# Hot.net
KiCad netlist of a schematic drawn in EAGLE
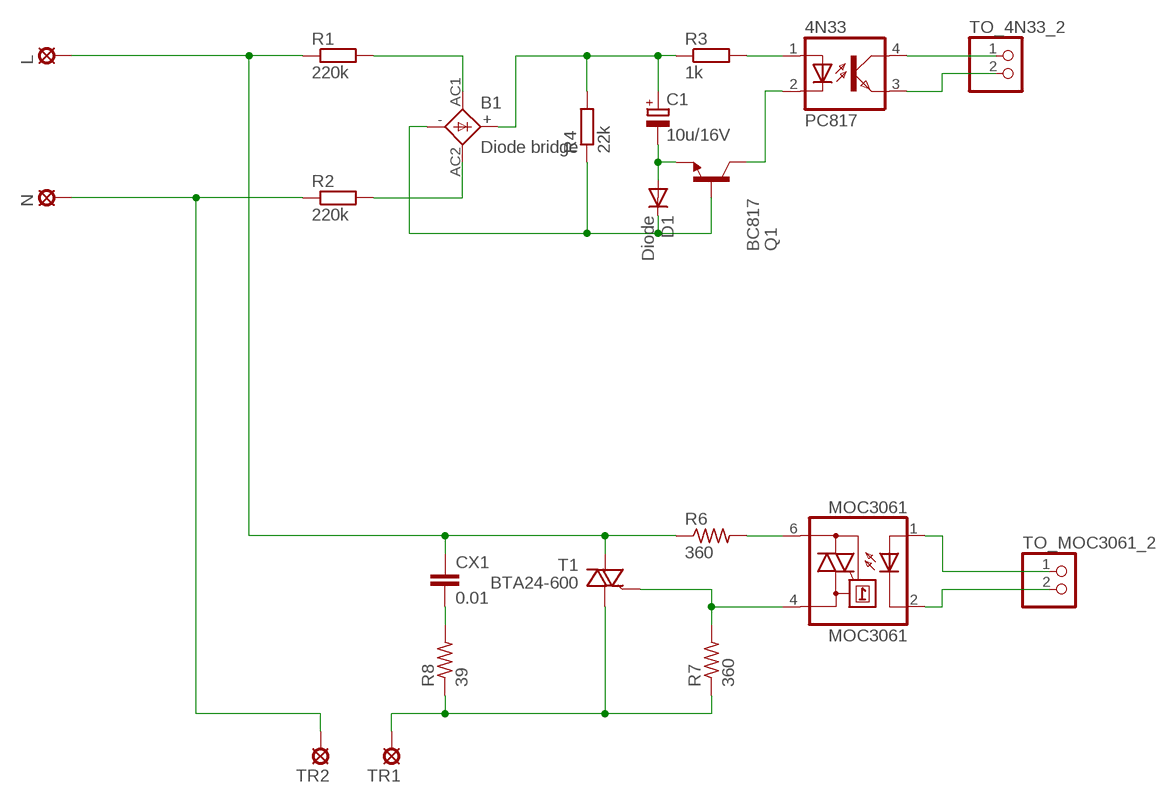
[diagram p0: schematic, sheet 1]

(export (version "E")
  (design (tool "Eeschema 10.0.6"))
  (components
    (comp (ref "4N33")
      (value "PC817")
      (footprint "eagle-import:DIL04")
      (libsource (lib "eagle-import") (part "PC817"))
    )
    (comp (ref "B1")
      (value "Diode bridge")
      (footprint "eagle-import:2KBB-R")
      (libsource (lib "eagle-import") (part "2KBB-R"))
    )
    (comp (ref "C1")
      (value "10u/16V")
      (footprint "eagle-import:E2,5-5")
      (libsource (lib "eagle-import") (part "CPOL-EUE2.5-5"))
    )
    (comp (ref "CX1")
      (value "0.01")
      (footprint "eagle-import:XC10B6")
      (libsource (lib "eagle-import") (part "CXXC10B6"))
    )
    (comp (ref "D1")
      (value "Diode")
      (footprint "eagle-import:DO-214AC")
      (libsource (lib "eagle-import") (part "DIODE-DO-214AC"))
    )
    (comp (ref "L")
      (value "LSP10")
      (footprint "eagle-import:LSP10")
      (libsource (lib "eagle-import") (part "LSP10"))
    )
    (comp (ref "MOC3061")
      (value "MOC3061")
      (footprint "eagle-import:DIL06")
      (libsource (lib "eagle-import") (part "IL410"))
    )
    (comp (ref "N")
      (value "LSP10")
      (footprint "eagle-import:LSP10")
      (libsource (lib "eagle-import") (part "LSP10"))
    )
    (comp (ref "Q1")
      (value "BC817")
      (footprint "eagle-import:SOT23-BEC")
      (libsource (lib "eagle-import") (part "BC817SMD-16LT1"))
    )
    (comp (ref "R1")
      (value "220k")
      (footprint "eagle-import:M1206")
      (libsource (lib "eagle-import") (part "R-EU_M1206"))
    )
    (comp (ref "R2")
      (value "220k")
      (footprint "eagle-import:M1206")
      (libsource (lib "eagle-import") (part "R-EU_M1206"))
    )
    (comp (ref "R3")
      (value "1k")
      (footprint "eagle-import:M1206")
      (libsource (lib "eagle-import") (part "R-EU_M1206"))
    )
    (comp (ref "R4")
      (value "22k")
      (footprint "eagle-import:M1206")
      (libsource (lib "eagle-import") (part "R-EU_M1206"))
    )
    (comp (ref "R6")
      (value "360")
      (footprint "eagle-import:VTA54")
      (libsource (lib "eagle-import") (part "R-US_VTA54"))
    )
    (comp (ref "R7")
      (value "360")
      (footprint "eagle-import:VTA54")
      (libsource (lib "eagle-import") (part "R-US_VTA54"))
    )
    (comp (ref "R8")
      (value "39")
      (footprint "eagle-import:VTA52")
      (libsource (lib "eagle-import") (part "R-US_VTA52"))
    )
    (comp (ref "T1")
      (value "BTA24-600")
      (footprint "eagle-import:TO220DS")
      (libsource (lib "eagle-import") (part "TIC225S"))
    )
    (comp (ref "TO_4N33_2")
      (value "PINHD-1X2")
      (footprint "eagle-import:1X02")
      (libsource (lib "eagle-import") (part "PINHD-1X2"))
    )
    (comp (ref "TO_MOC3061_2")
      (value "PINHD-1X2")
      (footprint "eagle-import:1X02")
      (libsource (lib "eagle-import") (part "PINHD-1X2"))
    )
    (comp (ref "TR1")
      (value "LSP10")
      (footprint "eagle-import:LSP10")
      (libsource (lib "eagle-import") (part "LSP10"))
    )
    (comp (ref "TR2")
      (value "LSP10")
      (footprint "eagle-import:LSP10")
      (libsource (lib "eagle-import") (part "LSP10"))
    )
  )
  (nets
    (net (code "1") (name "Net-(4N33-A)") (class "Default")
      (node (ref "4N33") (pin "1") (pinfunction "A_1") (pintype "passive"))
      (node (ref "R3") (pin "2") (pinfunction "2_2") (pintype "passive"))
    )
    (net (code "2") (name "Net-(4N33-C)") (class "Default")
      (node (ref "4N33") (pin "2") (pinfunction "C_2") (pintype "passive"))
      (node (ref "Q1") (pin "C") (pinfunction "C_C") (pintype "passive"))
    )
    (net (code "3") (name "Net-(4N33-COL)") (class "Default")
      (node (ref "4N33") (pin "4") (pinfunction "COL_4") (pintype "passive"))
      (node (ref "TO_4N33_2") (pin "1") (pinfunction "1_1") (pintype "passive"))
    )
    (net (code "4") (name "Net-(4N33-EMIT)") (class "Default")
      (node (ref "4N33") (pin "3") (pinfunction "EMIT_3") (pintype "passive"))
      (node (ref "TO_4N33_2") (pin "2") (pinfunction "2_2") (pintype "passive"))
    )
    (net (code "5") (name "Net-(B1-Pad+)") (class "Default")
      (node (ref "B1") (pin "+") (pinfunction "+_+") (pintype "passive"))
      (node (ref "C1") (pin "+") (pinfunction "+_+") (pintype "passive"))
      (node (ref "R3") (pin "1") (pinfunction "1_1") (pintype "passive"))
      (node (ref "R4") (pin "2") (pinfunction "2_2") (pintype "passive"))
    )
    (net (code "6") (name "Net-(B1-Pad-)") (class "Default")
      (node (ref "B1") (pin "-") (pinfunction "-_-") (pintype "passive"))
      (node (ref "D1") (pin "C") (pinfunction "C_C") (pintype "passive"))
      (node (ref "Q1") (pin "B") (pinfunction "B_B") (pintype "passive"))
      (node (ref "R4") (pin "1") (pinfunction "1_1") (pintype "passive"))
    )
    (net (code "7") (name "Net-(B1-PadAC1)") (class "Default")
      (node (ref "B1") (pin "AC1") (pinfunction "AC1_AC1") (pintype "passive"))
      (node (ref "R1") (pin "2") (pinfunction "2_2") (pintype "passive"))
    )
    (net (code "8") (name "Net-(B1-PadAC2)") (class "Default")
      (node (ref "B1") (pin "AC2") (pinfunction "AC2_AC2") (pintype "passive"))
      (node (ref "R2") (pin "2") (pinfunction "2_2") (pintype "passive"))
    )
    (net (code "9") (name "Net-(C1-Pad-)") (class "Default")
      (node (ref "C1") (pin "-") (pinfunction "-_-") (pintype "passive"))
      (node (ref "D1") (pin "A") (pinfunction "A_A") (pintype "passive"))
      (node (ref "Q1") (pin "E") (pinfunction "E_E") (pintype "passive"))
    )
    (net (code "10") (name "Net-(CX1-Pad1)") (class "Default")
      (node (ref "CX1") (pin "1") (pinfunction "1_1") (pintype "passive"))
      (node (ref "L") (pin "MP") (pinfunction "MP_MP") (pintype "passive"))
      (node (ref "R1") (pin "1") (pinfunction "1_1") (pintype "passive"))
      (node (ref "R6") (pin "1") (pinfunction "1_1") (pintype "passive"))
      (node (ref "T1") (pin "A2") (pinfunction "A2_A2") (pintype "passive"))
    )
    (net (code "11") (name "Net-(CX1-Pad2)") (class "Default")
      (node (ref "CX1") (pin "2") (pinfunction "2_2") (pintype "passive"))
      (node (ref "R8") (pin "2") (pinfunction "2_2") (pintype "passive"))
    )
    (net (code "12") (name "Net-(MOC3061-A)") (class "Default")
      (node (ref "MOC3061") (pin "1") (pinfunction "A_1") (pintype "passive"))
      (node (ref "TO_MOC3061_2") (pin "1") (pinfunction "1_1") (pintype "passive"))
    )
    (net (code "13") (name "Net-(MOC3061-A1)") (class "Default")
      (node (ref "MOC3061") (pin "4") (pinfunction "A1_4") (pintype "passive"))
      (node (ref "R7") (pin "2") (pinfunction "2_2") (pintype "passive"))
      (node (ref "T1") (pin "G") (pinfunction "G_G") (pintype "passive"))
    )
    (net (code "14") (name "Net-(MOC3061-A2)") (class "Default")
      (node (ref "MOC3061") (pin "6") (pinfunction "A2_6") (pintype "passive"))
      (node (ref "R6") (pin "2") (pinfunction "2_2") (pintype "passive"))
    )
    (net (code "15") (name "Net-(MOC3061-C)") (class "Default")
      (node (ref "MOC3061") (pin "2") (pinfunction "C_2") (pintype "passive"))
      (node (ref "TO_MOC3061_2") (pin "2") (pinfunction "2_2") (pintype "passive"))
    )
    (net (code "16") (name "Net-(N-PadMP)") (class "Default")
      (node (ref "N") (pin "MP") (pinfunction "MP_MP") (pintype "passive"))
      (node (ref "R2") (pin "1") (pinfunction "1_1") (pintype "passive"))
      (node (ref "TR2") (pin "MP") (pinfunction "MP_MP") (pintype "passive"))
    )
    (net (code "17") (name "Net-(R7-Pad1)") (class "Default")
      (node (ref "R7") (pin "1") (pinfunction "1_1") (pintype "passive"))
      (node (ref "R8") (pin "1") (pinfunction "1_1") (pintype "passive"))
      (node (ref "T1") (pin "A1") (pinfunction "A1_A1") (pintype "passive"))
      (node (ref "TR1") (pin "MP") (pinfunction "MP_MP") (pintype "passive"))
    )
  )
)
